# Mako_DSP_Power_R2_1.net
KiCad netlist of a schematic drawn in Altium Designer
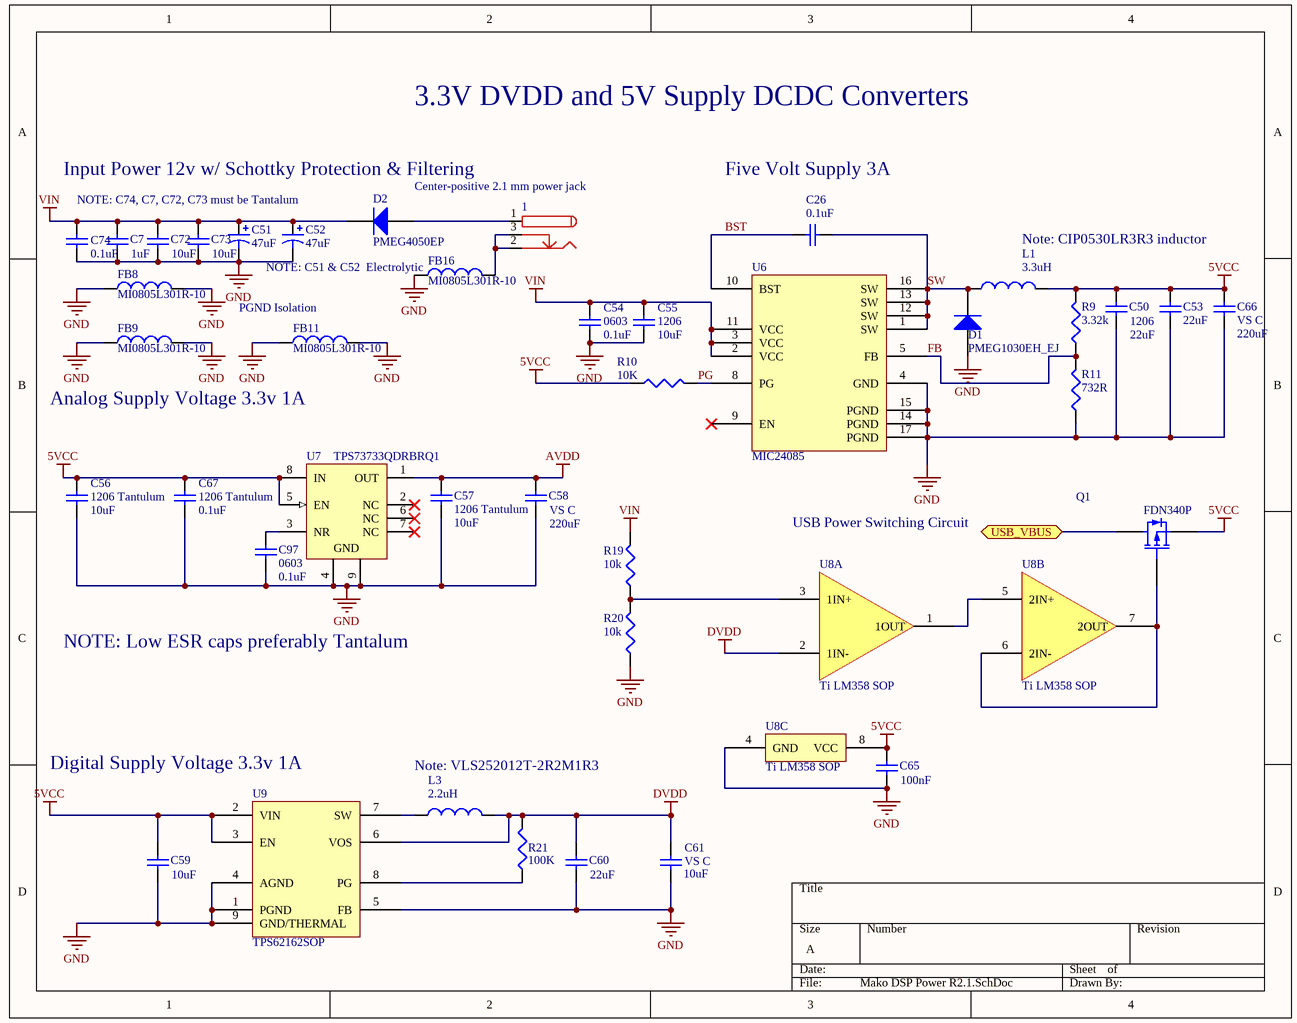
[diagram p0: Mako DSP Power R2.1.SchDoc]

(export (version "E")
  (design (tool "Eeschema 10.0.6"))
  (components
    (comp (ref "1")
      (value "Center-positive 2.1 mm power jack")
      (footprint "PJ-102AH")
      (description "Power jack")
      (fields (field (name "PUBLISHER") "Altium Limited"))
      (libsource (lib "Rascal") (part "PWR2.5"))
    )
    (comp (ref "C7")
      (value "1uF")
      (footprint "C1206")
      (description "Capacitor (Semiconductor SIM Model)")
      (fields (field (name "Comment") "Cap Semi") (field (name "PUBLISHER") "Altium Limited"))
      (libsource (lib "Miscellaneous Devices") (part "Cap Semi"))
    )
    (comp (ref "C26")
      (value "0.1uF")
      (footprint "1608[0603]")
      (description "Capacitor (Semiconductor SIM Model)")
      (fields (field (name "Comment") "Cap Semi") (field (name "PUBLISHER") "Altium Limited"))
      (libsource (lib "Miscellaneous Devices") (part "Cap Semi"))
    )
    (comp (ref "C50")
      (value "1206")
      (footprint "C1206")
      (description "Capacitor (Semiconductor SIM Model)")
      (fields (field (name "ALTIUM_VALUE") "22uF") (field (name "PUBLISHER") "Altium Limited"))
      (libsource (lib "Miscellaneous Devices") (part "Cap Semi"))
    )
    (comp (ref "C51")
      (value "47uF")
      (footprint "CAPPR2.5-6.3x5")
      (description "Polarized Capacitor (Radial)")
      (fields (field (name "Comment") "Cap Pol1") (field (name "PUBLISHER") "Altium Limited"))
      (libsource (lib "Miscellaneous Devices") (part "Cap Pol1"))
    )
    (comp (ref "C52")
      (value "47uF")
      (footprint "CAPPR2.5-6.3x5")
      (description "Polarized Capacitor (Radial)")
      (fields (field (name "Comment") "Cap Pol1") (field (name "PUBLISHER") "Altium Limited"))
      (libsource (lib "Miscellaneous Devices") (part "Cap Pol1"))
    )
    (comp (ref "C53")
      (value "22uF")
      (footprint "C1206")
      (description "Capacitor (Semiconductor SIM Model)")
      (fields (field (name "Comment") "Cap Semi") (field (name "PUBLISHER") "Altium Limited"))
      (libsource (lib "Miscellaneous Devices") (part "Cap Semi"))
    )
    (comp (ref "C54")
      (value "0603")
      (footprint "1608[0603]")
      (description "Capacitor (Semiconductor SIM Model)")
      (fields (field (name "ALTIUM_VALUE") "0.1uF") (field (name "PUBLISHER") "Altium Limited"))
      (libsource (lib "Miscellaneous Devices") (part "Cap Semi"))
    )
    (comp (ref "C55")
      (value "1206")
      (footprint "C1206")
      (description "Capacitor (Semiconductor SIM Model)")
      (fields (field (name "ALTIUM_VALUE") "10uF") (field (name "PUBLISHER") "Altium Limited"))
      (libsource (lib "Miscellaneous Devices") (part "Cap Semi"))
    )
    (comp (ref "C56")
      (value "1206 Tantulum")
      (footprint "C1206")
      (description "Capacitor (Semiconductor SIM Model)")
      (fields (field (name "ALTIUM_VALUE") "10uF") (field (name "PUBLISHER") "Altium Limited"))
      (libsource (lib "Miscellaneous Devices") (part "Cap Semi"))
    )
    (comp (ref "C57")
      (value "1206 Tantulum")
      (footprint "C1206")
      (description "Capacitor (Semiconductor SIM Model)")
      (fields (field (name "ALTIUM_VALUE") "10uF") (field (name "PUBLISHER") "Altium Limited"))
      (libsource (lib "Miscellaneous Devices") (part "Cap Semi"))
    )
    (comp (ref "C58")
      (value "VS C")
      (footprint "Panasonic VS C")
      (description "Capacitor (Semiconductor SIM Model)")
      (fields (field (name "ALTIUM_VALUE") "220uF") (field (name "PUBLISHER") "Altium Limited"))
      (libsource (lib "Miscellaneous Devices") (part "Cap Semi"))
    )
    (comp (ref "C59")
      (value "10uF")
      (footprint "C1206")
      (description "Capacitor (Semiconductor SIM Model)")
      (fields (field (name "Comment") "Cap Semi") (field (name "PUBLISHER") "Altium Limited"))
      (libsource (lib "Miscellaneous Devices") (part "Cap Semi"))
    )
    (comp (ref "C60")
      (value "22uF")
      (footprint "C1206")
      (description "Capacitor (Semiconductor SIM Model)")
      (fields (field (name "Comment") "Cap Semi") (field (name "PUBLISHER") "Altium Limited"))
      (libsource (lib "Miscellaneous Devices") (part "Cap Semi"))
    )
    (comp (ref "C61")
      (value "VS C")
      (footprint "Panasonic VS C")
      (description "Capacitor (Semiconductor SIM Model)")
      (fields (field (name "ALTIUM_VALUE") "10uF") (field (name "PUBLISHER") "Altium Limited"))
      (libsource (lib "Miscellaneous Devices") (part "Cap Semi"))
    )
    (comp (ref "C65")
      (value "100nF")
      (footprint "1608[0603]")
      (description "Capacitor (Semiconductor SIM Model)")
      (fields (field (name "Comment") "Cap Semi") (field (name "PUBLISHER") "Altium Limited"))
      (libsource (lib "Miscellaneous Devices") (part "Cap Semi"))
    )
    (comp (ref "C66")
      (value "VS C")
      (footprint "Panasonic VS C")
      (description "Capacitor (Semiconductor SIM Model)")
      (fields (field (name "ALTIUM_VALUE") "220uF") (field (name "PUBLISHER") "Altium Limited"))
      (libsource (lib "Miscellaneous Devices") (part "Cap Semi"))
    )
    (comp (ref "C67")
      (value "1206 Tantulum")
      (footprint "C1206")
      (description "Capacitor (Semiconductor SIM Model)")
      (fields (field (name "ALTIUM_VALUE") "0.1uF") (field (name "PUBLISHER") "Altium Limited"))
      (libsource (lib "Miscellaneous Devices") (part "Cap Semi"))
    )
    (comp (ref "C72")
      (value "10uF")
      (footprint "C1206")
      (description "Capacitor (Semiconductor SIM Model)")
      (fields (field (name "Comment") "Cap Semi") (field (name "PUBLISHER") "Altium Limited"))
      (libsource (lib "Miscellaneous Devices") (part "Cap Semi"))
    )
    (comp (ref "C73")
      (value "10uF")
      (footprint "C1206")
      (description "Capacitor (Semiconductor SIM Model)")
      (fields (field (name "Comment") "Cap Semi") (field (name "PUBLISHER") "Altium Limited"))
      (libsource (lib "Miscellaneous Devices") (part "Cap Semi"))
    )
    (comp (ref "C74")
      (value "0.1uF")
      (footprint "C1206")
      (description "Capacitor (Semiconductor SIM Model)")
      (fields (field (name "Comment") "Cap Semi") (field (name "PUBLISHER") "Altium Limited"))
      (libsource (lib "Miscellaneous Devices") (part "Cap Semi"))
    )
    (comp (ref "C97")
      (value "0603")
      (footprint "1608[0603]")
      (description "Capacitor (Semiconductor SIM Model)")
      (fields (field (name "ALTIUM_VALUE") "0.1uF") (field (name "PUBLISHER") "Altium Limited"))
      (libsource (lib "Miscellaneous Devices") (part "Cap Semi"))
    )
    (comp (ref "D1")
      (value "PMEG1030EH_EJ")
      (footprint "PMEG1030EH_EJ")
      (description "Default Diode")
      (fields (field (name "PUBLISHER") "Altium Limited"))
      (libsource (lib "") (part "Diode_1"))
    )
    (comp (ref "D2")
      (value "PMEG4050EP")
      (footprint "PMEG4050EP")
      (description "Default Diode")
      (fields (field (name "PUBLISHER") "Altium Limited"))
      (libsource (lib "Miscellaneous Devices") (part "Diode"))
    )
    (comp (ref "FB8")
      (value "MI0805L301R-10")
      (footprint "SM 0805 - gap trimmed")
      (description "Inductor")
      (fields (field (name "PUBLISHER") "Altium Limited"))
      (libsource (lib "Miscellaneous Devices") (part "Inductor"))
    )
    (comp (ref "FB9")
      (value "MI0805L301R-10")
      (footprint "SM 0805 - gap trimmed")
      (description "Inductor")
      (fields (field (name "PUBLISHER") "Altium Limited"))
      (libsource (lib "Miscellaneous Devices") (part "Inductor"))
    )
    (comp (ref "FB11")
      (value "MI0805L301R-10")
      (footprint "SM 0805 - gap trimmed")
      (description "Inductor")
      (fields (field (name "PUBLISHER") "Altium Limited"))
      (libsource (lib "Miscellaneous Devices") (part "Inductor"))
    )
    (comp (ref "FB16")
      (value "MI0805L301R-10")
      (footprint "SM 0805 - gap trimmed")
      (description "Inductor")
      (fields (field (name "PUBLISHER") "Altium Limited"))
      (libsource (lib "Miscellaneous Devices") (part "Inductor"))
    )
    (comp (ref "L1")
      (value "3.3uH")
      (footprint "CIP0530LR3R3")
      (description "Inductor")
      (fields (field (name "PUBLISHER") "Altium Limited"))
      (libsource (lib "Miscellaneous Devices") (part "Inductor"))
    )
    (comp (ref "L3")
      (value "2.2uH")
      (footprint "VLS252012T-2R2M1R3")
      (description "Inductor")
      (fields (field (name "PUBLISHER") "Altium Limited"))
      (libsource (lib "Miscellaneous Devices") (part "Inductor"))
    )
    (comp (ref "Q1")
      (value "FDN340P")
      (footprint "SOT23-3N")
      (description "P-Channel MOSFET")
      (fields (field (name "PUBLISHER") "Altium Limited"))
      (libsource (lib "Mako DSP Schematic Library") (part "FDN340P"))
    )
    (comp (ref "R9")
      (value "3.32k")
      (footprint "J1-0603")
      (description "Resistor")
      (fields (field (name "Comment") "Res3") (field (name "PUBLISHER") "Altium Limited"))
      (libsource (lib "Miscellaneous Devices") (part "Res3"))
    )
    (comp (ref "R10")
      (value "10K")
      (footprint "J1-0603")
      (description "Resistor")
      (fields (field (name "Comment") "Res3") (field (name "PUBLISHER") "Altium Limited"))
      (libsource (lib "Miscellaneous Devices") (part "Res3"))
    )
    (comp (ref "R11")
      (value "732R")
      (footprint "J1-0603")
      (description "Resistor")
      (fields (field (name "Comment") "Res3") (field (name "PUBLISHER") "Altium Limited"))
      (libsource (lib "Miscellaneous Devices") (part "Res3"))
    )
    (comp (ref "R19")
      (value "10k")
      (footprint "J1-0603")
      (description "Resistor")
      (fields (field (name "Comment") "Res3") (field (name "PUBLISHER") "Altium Limited"))
      (libsource (lib "Miscellaneous Devices") (part "Res3"))
    )
    (comp (ref "R20")
      (value "10k")
      (footprint "J1-0603")
      (description "Resistor")
      (fields (field (name "Comment") "Res3") (field (name "PUBLISHER") "Altium Limited"))
      (libsource (lib "Miscellaneous Devices") (part "Res3"))
    )
    (comp (ref "R21")
      (value "100K")
      (footprint "RESC2012L")
      (description "Resistor")
      (fields (field (name "Comment") "Res3") (field (name "PUBLISHER") "Altium Limited"))
      (libsource (lib "Miscellaneous Devices") (part "Res3"))
    )
    (comp (ref "U6")
      (value "MIC24085")
      (footprint "MIC24085-AYML")
      (libsource (lib "Adams Altium Library") (part "MIC24085"))
    )
    (comp (ref "U7")
      (value "TPS73733QDRBRQ1")
      (footprint "TI-DRB8-1750X1500TP_V")
      (fields (field (name "MANUFACTURER") "Texas Instruments"))
      (libsource (lib "TI Power Management Linear Regulator Single Channel LDO (400-7500mA)") (part "TPS73733QDRBRQ1"))
    )
    (comp (ref "U8")
      (value "Ti LM358 SOP")
      (footprint "LM358")
      (libsource (lib "Mako DSP Schematic Library") (part "LM358_Symbol"))
    )
    (comp (ref "U9")
      (value "TPS62162SOP")
      (footprint "TPS62162SOP")
      (libsource (lib "Adams Altium Library") (part "TPS62162SOP"))
    )
  )
  (nets
    (net (code "1") (name "/BST") (class "Default")
      (node (ref "C26") (pin "2") (pinfunction "2_2") (pintype "passive"))
      (node (ref "U6") (pin "10") (pinfunction "BST_10") (pintype "passive"))
    )
    (net (code "2") (name "/FB") (class "Default")
      (node (ref "R11") (pin "2") (pinfunction "2_2") (pintype "passive"))
      (node (ref "R9") (pin "1") (pinfunction "1_1") (pintype "passive"))
      (node (ref "U6") (pin "5") (pinfunction "FB_5") (pintype "passive"))
    )
    (net (code "3") (name "/PG") (class "Default")
      (node (ref "R10") (pin "2") (pinfunction "2_2") (pintype "passive"))
      (node (ref "U6") (pin "8") (pinfunction "PG_8") (pintype "passive"))
    )
    (net (code "4") (name "/SW") (class "Default")
      (node (ref "C26") (pin "1") (pinfunction "1_1") (pintype "passive"))
      (node (ref "D1") (pin "2") (pinfunction "K_2") (pintype "passive"))
      (node (ref "L1") (pin "1") (pinfunction "1_1") (pintype "passive"))
      (node (ref "U6") (pin "1") (pinfunction "SW_1") (pintype "passive"))
      (node (ref "U6") (pin "12") (pinfunction "SW_12") (pintype "passive"))
      (node (ref "U6") (pin "13") (pinfunction "SW_13") (pintype "passive"))
      (node (ref "U6") (pin "16") (pinfunction "SW_16") (pintype "passive"))
    )
    (net (code "5") (name "/USB_VBUS") (class "Default")
      (node (ref "Q1") (pin "3") (pinfunction "S_3") (pintype "passive"))
    )
    (net (code "6") (name "5VCC") (class "Default")
      (node (ref "C50") (pin "2") (pinfunction "2_2") (pintype "passive"))
      (node (ref "C53") (pin "1") (pinfunction "1_1") (pintype "passive"))
      (node (ref "C56") (pin "1") (pinfunction "1_1") (pintype "passive"))
      (node (ref "C59") (pin "2") (pinfunction "2_2") (pintype "passive"))
      (node (ref "C65") (pin "1") (pinfunction "1_1") (pintype "passive"))
      (node (ref "C66") (pin "2") (pinfunction "2_2") (pintype "passive"))
      (node (ref "C67") (pin "2") (pinfunction "2_2") (pintype "passive"))
      (node (ref "L1") (pin "2") (pinfunction "2_2") (pintype "passive"))
      (node (ref "Q1") (pin "2") (pinfunction "D_2") (pintype "passive"))
      (node (ref "R10") (pin "1") (pinfunction "1_1") (pintype "passive"))
      (node (ref "R9") (pin "2") (pinfunction "2_2") (pintype "passive"))
      (node (ref "U7") (pin "5") (pinfunction "EN_5") (pintype "input"))
      (node (ref "U7") (pin "8") (pinfunction "IN_8") (pintype "power_in"))
      (node (ref "U8") (pin "8") (pinfunction "VCC_8") (pintype "passive"))
      (node (ref "U9") (pin "2") (pinfunction "VIN_2") (pintype "passive"))
      (node (ref "U9") (pin "3") (pinfunction "EN_3") (pintype "passive"))
    )
    (net (code "7") (name "AVDD") (class "Default")
      (node (ref "C57") (pin "1") (pinfunction "1_1") (pintype "passive"))
      (node (ref "C58") (pin "1") (pinfunction "1_1") (pintype "passive"))
      (node (ref "U7") (pin "1") (pinfunction "OUT_1") (pintype "power_in"))
    )
    (net (code "8") (name "DVDD") (class "Default")
      (node (ref "C60") (pin "2") (pinfunction "2_2") (pintype "passive"))
      (node (ref "C61") (pin "1") (pinfunction "1_1") (pintype "passive"))
      (node (ref "L3") (pin "2") (pinfunction "2_2") (pintype "passive"))
      (node (ref "R21") (pin "2") (pinfunction "2_2") (pintype "passive"))
      (node (ref "U8") (pin "2") (pinfunction "1IN-_2") (pintype "passive"))
      (node (ref "U9") (pin "6") (pinfunction "VOS_6") (pintype "passive"))
    )
    (net (code "9") (name "GND") (class "Default")
      (node (ref "C50") (pin "1") (pinfunction "1_1") (pintype "passive"))
      (node (ref "C51") (pin "2") (pinfunction "2_2") (pintype "passive"))
      (node (ref "C52") (pin "2") (pinfunction "2_2") (pintype "passive"))
      (node (ref "C53") (pin "2") (pinfunction "2_2") (pintype "passive"))
      (node (ref "C54") (pin "1") (pinfunction "1_1") (pintype "passive"))
      (node (ref "C55") (pin "1") (pinfunction "1_1") (pintype "passive"))
      (node (ref "C56") (pin "2") (pinfunction "2_2") (pintype "passive"))
      (node (ref "C57") (pin "2") (pinfunction "2_2") (pintype "passive"))
      (node (ref "C58") (pin "2") (pinfunction "2_2") (pintype "passive"))
      (node (ref "C59") (pin "1") (pinfunction "1_1") (pintype "passive"))
      (node (ref "C60") (pin "1") (pinfunction "1_1") (pintype "passive"))
      (node (ref "C61") (pin "2") (pinfunction "2_2") (pintype "passive"))
      (node (ref "C65") (pin "2") (pinfunction "2_2") (pintype "passive"))
      (node (ref "C66") (pin "1") (pinfunction "1_1") (pintype "passive"))
      (node (ref "C67") (pin "1") (pinfunction "1_1") (pintype "passive"))
      (node (ref "C7") (pin "1") (pinfunction "1_1") (pintype "passive"))
      (node (ref "C72") (pin "1") (pinfunction "1_1") (pintype "passive"))
      (node (ref "C73") (pin "1") (pinfunction "1_1") (pintype "passive"))
      (node (ref "C74") (pin "1") (pinfunction "1_1") (pintype "passive"))
      (node (ref "C97") (pin "1") (pinfunction "1_1") (pintype "passive"))
      (node (ref "D1") (pin "1") (pinfunction "A_1") (pintype "passive"))
      (node (ref "FB11") (pin "1") (pinfunction "1_1") (pintype "passive"))
      (node (ref "FB11") (pin "2") (pinfunction "2_2") (pintype "passive"))
      (node (ref "FB16") (pin "1") (pinfunction "1_1") (pintype "passive"))
      (node (ref "FB8") (pin "1") (pinfunction "1_1") (pintype "passive"))
      (node (ref "FB8") (pin "2") (pinfunction "2_2") (pintype "passive"))
      (node (ref "FB9") (pin "1") (pinfunction "1_1") (pintype "passive"))
      (node (ref "FB9") (pin "2") (pinfunction "2_2") (pintype "passive"))
      (node (ref "R11") (pin "1") (pinfunction "1_1") (pintype "passive"))
      (node (ref "R20") (pin "1") (pinfunction "1_1") (pintype "passive"))
      (node (ref "U6") (pin "14") (pinfunction "PGND_14") (pintype "passive"))
      (node (ref "U6") (pin "15") (pinfunction "PGND_15") (pintype "passive"))
      (node (ref "U6") (pin "17") (pinfunction "PGND_17") (pintype "passive"))
      (node (ref "U6") (pin "4") (pinfunction "GND_4") (pintype "passive"))
      (node (ref "U7") (pin "4") (pinfunction "GND_4") (pintype "power_in"))
      (node (ref "U7") (pin "9") (pinfunction "GND_9") (pintype "power_in"))
      (node (ref "U8") (pin "4") (pinfunction "GND_4") (pintype "passive"))
      (node (ref "U9") (pin "1") (pinfunction "PGND_1") (pintype "passive"))
      (node (ref "U9") (pin "4") (pinfunction "AGND_4") (pintype "passive"))
      (node (ref "U9") (pin "5") (pinfunction "FB_5") (pintype "passive"))
      (node (ref "U9") (pin "9") (pinfunction "GND/THERMAL_9") (pintype "passive"))
    )
    (net (code "10") (name "Net-(1-Pad2)") (class "Default")
      (node (ref "1") (pin "2") (pinfunction "2_2") (pintype "power_in"))
      (node (ref "1") (pin "3") (pinfunction "3_3") (pintype "power_in"))
      (node (ref "FB16") (pin "2") (pinfunction "2_2") (pintype "passive"))
    )
    (net (code "11") (name "Net-(D2-K)") (class "Default")
      (node (ref "1") (pin "1") (pinfunction "1_1") (pintype "power_in"))
      (node (ref "D2") (pin "2") (pinfunction "K_2") (pintype "passive"))
    )
    (net (code "12") (name "Net-(Q1-G)") (class "Default")
      (node (ref "Q1") (pin "1") (pinfunction "G_1") (pintype "passive"))
      (node (ref "U8") (pin "6") (pinfunction "2IN-_6") (pintype "passive"))
      (node (ref "U8") (pin "7") (pinfunction "2OUT_7") (pintype "passive"))
    )
    (net (code "13") (name "Net-(U7-NR)") (class "Default")
      (node (ref "C97") (pin "2") (pinfunction "2_2") (pintype "passive"))
      (node (ref "U7") (pin "3") (pinfunction "NR_3") (pintype "passive"))
    )
    (net (code "14") (name "Net-(U8A-1IN+)") (class "Default")
      (node (ref "R19") (pin "1") (pinfunction "1_1") (pintype "passive"))
      (node (ref "R20") (pin "2") (pinfunction "2_2") (pintype "passive"))
      (node (ref "U8") (pin "3") (pinfunction "1IN+_3") (pintype "passive"))
    )
    (net (code "15") (name "Net-(U8A-1OUT)") (class "Default")
      (node (ref "U8") (pin "1") (pinfunction "1OUT_1") (pintype "passive"))
      (node (ref "U8") (pin "5") (pinfunction "2IN+_5") (pintype "passive"))
    )
    (net (code "16") (name "Net-(U9-PG)") (class "Default")
      (node (ref "R21") (pin "1") (pinfunction "1_1") (pintype "passive"))
      (node (ref "U9") (pin "8") (pinfunction "PG_8") (pintype "passive"))
    )
    (net (code "17") (name "Net-(U9-SW)") (class "Default")
      (node (ref "L3") (pin "1") (pinfunction "1_1") (pintype "passive"))
      (node (ref "U9") (pin "7") (pinfunction "SW_7") (pintype "passive"))
    )
    (net (code "18") (name "VIN") (class "Default")
      (node (ref "C51") (pin "1") (pinfunction "1_1") (pintype "passive"))
      (node (ref "C52") (pin "1") (pinfunction "1_1") (pintype "passive"))
      (node (ref "C54") (pin "2") (pinfunction "2_2") (pintype "passive"))
      (node (ref "C55") (pin "2") (pinfunction "2_2") (pintype "passive"))
      (node (ref "C7") (pin "2") (pinfunction "2_2") (pintype "passive"))
      (node (ref "C72") (pin "2") (pinfunction "2_2") (pintype "passive"))
      (node (ref "C73") (pin "2") (pinfunction "2_2") (pintype "passive"))
      (node (ref "C74") (pin "2") (pinfunction "2_2") (pintype "passive"))
      (node (ref "D2") (pin "1") (pinfunction "A_1") (pintype "passive"))
      (node (ref "R19") (pin "2") (pinfunction "2_2") (pintype "passive"))
      (node (ref "U6") (pin "11") (pinfunction "VCC_11") (pintype "passive"))
      (node (ref "U6") (pin "2") (pinfunction "VCC_2") (pintype "passive"))
      (node (ref "U6") (pin "3") (pinfunction "VCC_3") (pintype "passive"))
    )
    (net (code "19") (name "unconnected-(U6-EN-Pad9)") (class "Default")
      (node (ref "U6") (pin "9") (pinfunction "EN_9") (pintype "passive+no_connect"))
    )
    (net (code "20") (name "unconnected-(U6-NC-Pad6)") (class "Default")
      (node (ref "U6") (pin "6") (pinfunction "NC_6") (pintype "passive"))
    )
    (net (code "21") (name "unconnected-(U6-NC-Pad7)") (class "Default")
      (node (ref "U6") (pin "7") (pinfunction "NC_7") (pintype "passive"))
    )
    (net (code "22") (name "unconnected-(U7-NC-Pad2)") (class "Default")
      (node (ref "U7") (pin "2") (pinfunction "NC_2") (pintype "passive+no_connect"))
    )
    (net (code "23") (name "unconnected-(U7-NC-Pad6)") (class "Default")
      (node (ref "U7") (pin "6") (pinfunction "NC_6") (pintype "passive+no_connect"))
    )
    (net (code "24") (name "unconnected-(U7-NC-Pad7)") (class "Default")
      (node (ref "U7") (pin "7") (pinfunction "NC_7") (pintype "passive+no_connect"))
    )
  )
)
